# Filter-5.net
KiCad netlist of a schematic drawn in Altium Designer
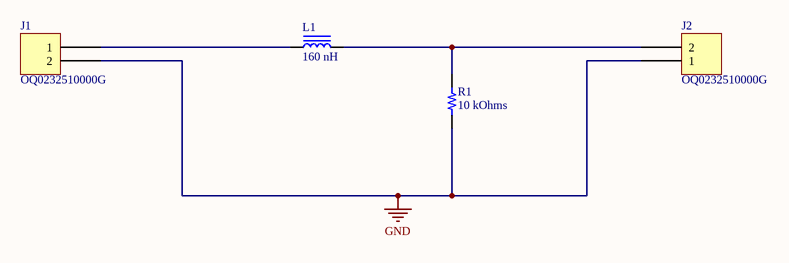
[diagram p0: Filter-5.SchDoc]

(export (version "E")
  (design (tool "Eeschema 10.0.6"))
  (components
    (comp (ref "J1")
      (value "OQ0232510000G")
      (footprint "FCI 06-381-2PIN")
      (description "TERM BLOCK HDR 2POS 90DEG 3.81MM")
      (fields (field (name "MANUFACTURER") "Amphenol Anytek"))
      (libsource (lib "Celestial Altium Library - altium_library") (part "2 Pin"))
    )
    (comp (ref "J2")
      (value "OQ0232510000G")
      (footprint "FCI 06-381-2PIN")
      (description "TERM BLOCK HDR 2POS 90DEG 3.81MM")
      (fields (field (name "MANUFACTURER") "Amphenol Anytek"))
      (libsource (lib "") (part "2 Pin_1"))
    )
    (comp (ref "L1")
      (value "160 nH")
      (footprint "IND 0402_1005 RF WW")
      (description "FIXED IND 160NH 480MA 330MOHM SM")
      (fields
        (field (name "PART NUMBER") "LQW15CNR16J00D")
        (field (name "MANUFACTURER") "Murata Electronics")
      )
      (libsource (lib "Celestial Altium Library - altium_library") (part "Inductor"))
    )
    (comp (ref "R1")
      (value "10 kOhms")
      (footprint "RES 0603_1608")
      (description "RES 10K OHM 0.1% 1/16W 0603")
      (fields
        (field (name "PART NUMBER") "RNCS0603BKE10K0")
        (field (name "MANUFACTURER") "Stackpole Electronics Inc")
      )
      (libsource (lib "Celestial Altium Library - altium_library") (part "Resistor"))
    )
  )
  (nets
    (net (code "1") (name "GND") (class "Default")
      (node (ref "J1") (pin "2") (pinfunction "2_2") (pintype "passive"))
      (node (ref "J2") (pin "1") (pinfunction "1_1") (pintype "passive"))
      (node (ref "R1") (pin "1") (pinfunction "1_1") (pintype "passive"))
    )
    (net (code "2") (name "Net-(J1-Pad1)") (class "Default")
      (node (ref "J1") (pin "1") (pinfunction "1_1") (pintype "passive"))
      (node (ref "L1") (pin "1") (pinfunction "1_1") (pintype "passive"))
    )
    (net (code "3") (name "Net-(J2-Pad2)") (class "Default")
      (node (ref "J2") (pin "2") (pinfunction "2_2") (pintype "passive"))
      (node (ref "L1") (pin "2") (pinfunction "2_2") (pintype "passive"))
      (node (ref "R1") (pin "2") (pinfunction "2_2") (pintype "passive"))
    )
  )
)
